# Power.net
KiCad netlist of a schematic drawn in Altium Designer
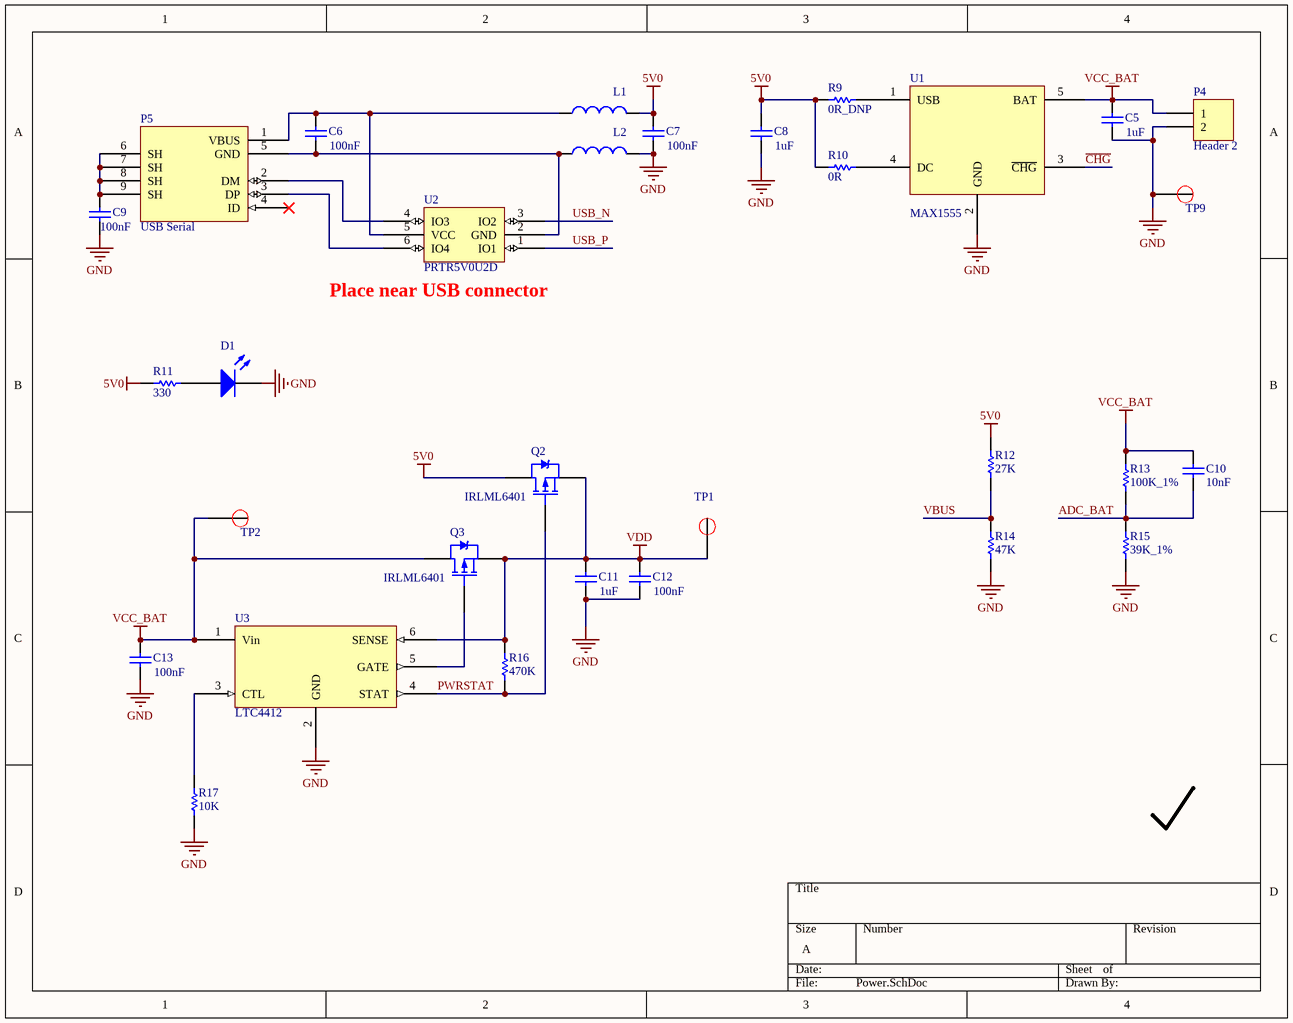
[diagram p0: Power.SchDoc]

(export (version "E")
  (design (tool "Eeschema 10.0.6"))
  (components
    (comp (ref "C5")
      (value "1uF")
      (footprint "0603PKG")
      (description "Capacitor")
      (fields (field (name "Comment") "Cap") (field (name "PUBLISHER") "Altium Limited"))
      (libsource (lib "Miscellaneous Devices") (part "Cap"))
    )
    (comp (ref "C6")
      (value "100nF")
      (footprint "C0805")
      (description "Capacitor")
      (fields (field (name "Comment") "Cap") (field (name "PUBLISHER") "Altium Limited"))
      (libsource (lib "Miscellaneous Devices") (part "Cap"))
    )
    (comp (ref "C7")
      (value "100nF")
      (footprint "C0805")
      (description "Capacitor")
      (fields (field (name "Comment") "Cap") (field (name "PUBLISHER") "Altium Limited"))
      (libsource (lib "Miscellaneous Devices") (part "Cap"))
    )
    (comp (ref "C8")
      (value "1uF")
      (footprint "0603PKG")
      (description "Capacitor")
      (fields (field (name "Comment") "Cap") (field (name "PUBLISHER") "Altium Limited"))
      (libsource (lib "Miscellaneous Devices") (part "Cap"))
    )
    (comp (ref "C9")
      (value "100nF")
      (footprint "C0805")
      (description "Capacitor")
      (fields (field (name "Comment") "Cap") (field (name "PUBLISHER") "Altium Limited"))
      (libsource (lib "Miscellaneous Devices") (part "Cap"))
    )
    (comp (ref "C10")
      (value "10nF")
      (footprint "0603PKG")
      (description "Capacitor (Semiconductor SIM Model)")
      (fields (field (name "Comment") "Cap Semi") (field (name "PUBLISHER") "Altium Limited"))
      (libsource (lib "Miscellaneous Devices") (part "Cap Semi"))
    )
    (comp (ref "C11")
      (value "1uF")
      (footprint "0603PKG")
      (description "Capacitor")
      (fields (field (name "Comment") "Cap") (field (name "PUBLISHER") "Altium Limited"))
      (libsource (lib "Miscellaneous Devices") (part "Cap"))
    )
    (comp (ref "C12")
      (value "100nF")
      (footprint "0603PKG")
      (description "Capacitor")
      (fields (field (name "Comment") "Cap") (field (name "PUBLISHER") "Altium Limited"))
      (libsource (lib "Miscellaneous Devices") (part "Cap"))
    )
    (comp (ref "C13")
      (value "100nF")
      (footprint "0603PKG")
      (description "Capacitor")
      (fields (field (name "Comment") "Cap") (field (name "PUBLISHER") "Altium Limited"))
      (libsource (lib "Miscellaneous Devices") (part "Cap"))
    )
    (comp (ref "D1")
      (value "LED0")
      (footprint "C0805")
      (description "Typical INFRARED GaAs LED")
      (fields (field (name "PUBLISHER") "Altium Limited"))
      (libsource (lib "Miscellaneous Devices") (part "LED0"))
    )
    (comp (ref "L1")
      (value "Ferrite Bead")
      (footprint "C0805")
      (description "Inductor")
      (fields (field (name "PUBLISHER") "Altium Limited"))
      (libsource (lib "Miscellaneous Devices") (part "Inductor"))
    )
    (comp (ref "L2")
      (value "Ferrite Bead")
      (footprint "C0805")
      (description "Inductor")
      (fields (field (name "PUBLISHER") "Altium Limited"))
      (libsource (lib "Miscellaneous Devices") (part "Inductor"))
    )
    (comp (ref "P4")
      (value "Header 2")
      (footprint "XH_2Pin_RA")
      (description "Header, 2-Pin")
      (fields (field (name "PUBLISHER") "Altium Limited"))
      (libsource (lib "Miscellaneous Connectors") (part "Header 2"))
    )
    (comp (ref "P5")
      (value "USB Serial")
      (footprint "Mini USB")
      (libsource (lib "Connector_IntLib") (part "Mini USB"))
    )
    (comp (ref "Q2")
      (value "IRLML6401")
      (footprint "SOT23")
      (description "P-Channel Power MOSFET")
      (fields (field (name "PUBLISHER") "Altium Limited"))
      (libsource (lib "Miscellaneous Devices") (part "PMOS-2"))
    )
    (comp (ref "Q3")
      (value "IRLML6401")
      (footprint "SOT23")
      (description "P-Channel Power MOSFET")
      (fields (field (name "PUBLISHER") "Altium Limited"))
      (libsource (lib "Miscellaneous Devices") (part "PMOS-2"))
    )
    (comp (ref "R9")
      (value "0R_DNP")
      (footprint "0603PKG")
      (description "Semiconductor Resistor")
      (fields (field (name "Comment") "Res Semi") (field (name "PUBLISHER") "Altium Limited"))
      (libsource (lib "Miscellaneous Devices") (part "Res Semi"))
    )
    (comp (ref "R10")
      (value "0R")
      (footprint "0603PKG")
      (description "Semiconductor Resistor")
      (fields (field (name "Comment") "Res Semi") (field (name "PUBLISHER") "Altium Limited"))
      (libsource (lib "Miscellaneous Devices") (part "Res Semi"))
    )
    (comp (ref "R11")
      (value "330")
      (footprint "0603PKG")
      (description "Semiconductor Resistor")
      (fields (field (name "Comment") "Res Semi") (field (name "PUBLISHER") "Altium Limited"))
      (libsource (lib "Miscellaneous Devices") (part "Res Semi"))
    )
    (comp (ref "R12")
      (value "27K")
      (footprint "0603PKG")
      (description "Semiconductor Resistor")
      (fields (field (name "Comment") "Res Semi") (field (name "PUBLISHER") "Altium Limited"))
      (libsource (lib "Miscellaneous Devices") (part "Res Semi"))
    )
    (comp (ref "R13")
      (value "100K_1%")
      (footprint "0603PKG")
      (description "Semiconductor Resistor")
      (fields (field (name "Comment") "Res Semi") (field (name "PUBLISHER") "Altium Limited"))
      (libsource (lib "Miscellaneous Devices") (part "Res Semi"))
    )
    (comp (ref "R14")
      (value "47K")
      (footprint "0603PKG")
      (description "Semiconductor Resistor")
      (fields (field (name "Comment") "Res Semi") (field (name "PUBLISHER") "Altium Limited"))
      (libsource (lib "Miscellaneous Devices") (part "Res Semi"))
    )
    (comp (ref "R15")
      (value "39K_1%")
      (footprint "0603PKG")
      (description "Semiconductor Resistor")
      (fields (field (name "Comment") "Res Semi") (field (name "PUBLISHER") "Altium Limited"))
      (libsource (lib "Miscellaneous Devices") (part "Res Semi"))
    )
    (comp (ref "R16")
      (value "470K")
      (footprint "0603PKG")
      (description "Semiconductor Resistor")
      (fields (field (name "Comment") "Res Semi") (field (name "PUBLISHER") "Altium Limited"))
      (libsource (lib "Miscellaneous Devices") (part "Res Semi"))
    )
    (comp (ref "R17")
      (value "10K")
      (footprint "0603PKG")
      (description "Semiconductor Resistor")
      (fields (field (name "Comment") "Res Semi") (field (name "PUBLISHER") "Altium Limited"))
      (libsource (lib "Miscellaneous Devices") (part "Res Semi"))
    )
    (comp (ref "TP1")
      (value "TP")
      (footprint "TP_15")
      (libsource (lib "Connector_IntLib") (part "Test Point"))
    )
    (comp (ref "TP2")
      (value "TP")
      (footprint "TP_15")
      (libsource (lib "Connector_IntLib") (part "Test Point"))
    )
    (comp (ref "TP9")
      (value "TP")
      (footprint "TP_15")
      (libsource (lib "Connector_IntLib") (part "Test Point"))
    )
    (comp (ref "U1")
      (value "MAX1555")
      (footprint "SOT23-5")
      (description "1-Cell Li+  Battery Chargers")
      (libsource (lib "Connector_IntLib") (part "MAX1555"))
    )
    (comp (ref "U2")
      (value "PRTR5V0U2D")
      (footprint "SOT457")
      (description "TVS Zener")
      (libsource (lib "Connector_IntLib") (part "PRTR5V0U2D"))
    )
    (comp (ref "U3")
      (value "LTC4412")
      (footprint "SOT23-6")
      (description "Low Loss PowerPath™  Controller in ThinSOT")
      (libsource (lib "Connector_IntLib") (part "LTC4412"))
    )
  )
  (nets
    (net (code "1") (name "/ADC_BAT") (class "Default")
      (node (ref "C10") (pin "2") (pinfunction "2_2") (pintype "passive"))
      (node (ref "R13") (pin "1") (pinfunction "1_1") (pintype "passive"))
      (node (ref "R15") (pin "2") (pinfunction "2_2") (pintype "passive"))
    )
    (net (code "2") (name "/PWRSTAT") (class "Default")
      (node (ref "Q2") (pin "1") (pinfunction "G_1") (pintype "passive"))
      (node (ref "R16") (pin "1") (pinfunction "1_1") (pintype "passive"))
      (node (ref "U3") (pin "4") (pinfunction "STAT_4") (pintype "output"))
    )
    (net (code "3") (name "/USB_N") (class "Default")
      (node (ref "U2") (pin "3") (pinfunction "IO2_3") (pintype "bidirectional"))
    )
    (net (code "4") (name "/USB_P") (class "Default")
      (node (ref "U2") (pin "1") (pinfunction "IO1_1") (pintype "bidirectional"))
    )
    (net (code "5") (name "/VBUS") (class "Default")
      (node (ref "R12") (pin "1") (pinfunction "1_1") (pintype "passive"))
      (node (ref "R14") (pin "2") (pinfunction "2_2") (pintype "passive"))
    )
    (net (code "6") (name "/~{CHG}") (class "Default")
      (node (ref "U1") (pin "3") (pinfunction "~{CHG}_3") (pintype "open_collector"))
    )
    (net (code "7") (name "5V0") (class "Default")
      (node (ref "C7") (pin "2") (pinfunction "2_2") (pintype "passive"))
      (node (ref "C8") (pin "2") (pinfunction "2_2") (pintype "passive"))
      (node (ref "L1") (pin "2") (pinfunction "2_2") (pintype "passive"))
      (node (ref "Q2") (pin "3") (pinfunction "D_3") (pintype "passive"))
      (node (ref "R10") (pin "1") (pinfunction "1_1") (pintype "passive"))
      (node (ref "R11") (pin "2") (pinfunction "2_2") (pintype "passive"))
      (node (ref "R12") (pin "2") (pinfunction "2_2") (pintype "passive"))
      (node (ref "R9") (pin "1") (pinfunction "1_1") (pintype "passive"))
    )
    (net (code "8") (name "GND") (class "Default")
      (node (ref "C11") (pin "1") (pinfunction "1_1") (pintype "passive"))
      (node (ref "C12") (pin "1") (pinfunction "1_1") (pintype "passive"))
      (node (ref "C13") (pin "1") (pinfunction "1_1") (pintype "passive"))
      (node (ref "C5") (pin "1") (pinfunction "1_1") (pintype "passive"))
      (node (ref "C7") (pin "1") (pinfunction "1_1") (pintype "passive"))
      (node (ref "C8") (pin "1") (pinfunction "1_1") (pintype "passive"))
      (node (ref "C9") (pin "1") (pinfunction "1_1") (pintype "passive"))
      (node (ref "D1") (pin "2") (pinfunction "K_2") (pintype "passive"))
      (node (ref "L2") (pin "2") (pinfunction "2_2") (pintype "passive"))
      (node (ref "P4") (pin "2") (pinfunction "2_2") (pintype "passive"))
      (node (ref "R14") (pin "1") (pinfunction "1_1") (pintype "passive"))
      (node (ref "R15") (pin "1") (pinfunction "1_1") (pintype "passive"))
      (node (ref "R17") (pin "1") (pinfunction "1_1") (pintype "passive"))
      (node (ref "TP9") (pin "1") (pinfunction "1_1") (pintype "passive"))
      (node (ref "U1") (pin "2") (pinfunction "GND_2") (pintype "power_in"))
      (node (ref "U3") (pin "2") (pinfunction "GND_2") (pintype "power_in"))
    )
    (net (code "9") (name "Net-(C9-Pad2)") (class "Default")
      (node (ref "C9") (pin "2") (pinfunction "2_2") (pintype "passive"))
      (node (ref "P5") (pin "6") (pinfunction "SH_6") (pintype "passive"))
      (node (ref "P5") (pin "7") (pinfunction "SH_7") (pintype "passive"))
      (node (ref "P5") (pin "8") (pinfunction "SH_8") (pintype "passive"))
      (node (ref "P5") (pin "9") (pinfunction "SH_9") (pintype "passive"))
    )
    (net (code "10") (name "Net-(D1-A)") (class "Default")
      (node (ref "D1") (pin "1") (pinfunction "A_1") (pintype "passive"))
      (node (ref "R11") (pin "1") (pinfunction "1_1") (pintype "passive"))
    )
    (net (code "11") (name "Net-(P5-DM)") (class "Default")
      (node (ref "P5") (pin "2") (pinfunction "DM_2") (pintype "bidirectional"))
      (node (ref "U2") (pin "4") (pinfunction "IO3_4") (pintype "bidirectional"))
    )
    (net (code "12") (name "Net-(P5-DP)") (class "Default")
      (node (ref "P5") (pin "3") (pinfunction "DP_3") (pintype "bidirectional"))
      (node (ref "U2") (pin "6") (pinfunction "IO4_6") (pintype "bidirectional"))
    )
    (net (code "13") (name "Net-(P5-GND)") (class "Default")
      (node (ref "C6") (pin "1") (pinfunction "1_1") (pintype "passive"))
      (node (ref "L2") (pin "1") (pinfunction "1_1") (pintype "passive"))
      (node (ref "P5") (pin "5") (pinfunction "GND_5") (pintype "power_in"))
      (node (ref "U2") (pin "2") (pinfunction "GND_2") (pintype "power_in"))
    )
    (net (code "14") (name "Net-(P5-VBUS)") (class "Default")
      (node (ref "C6") (pin "2") (pinfunction "2_2") (pintype "passive"))
      (node (ref "L1") (pin "1") (pinfunction "1_1") (pintype "passive"))
      (node (ref "P5") (pin "1") (pinfunction "VBUS_1") (pintype "power_in"))
      (node (ref "U2") (pin "5") (pinfunction "VCC_5") (pintype "power_in"))
    )
    (net (code "15") (name "Net-(Q3-G)") (class "Default")
      (node (ref "Q3") (pin "1") (pinfunction "G_1") (pintype "passive"))
      (node (ref "U3") (pin "5") (pinfunction "GATE_5") (pintype "output"))
    )
    (net (code "16") (name "Net-(U1-DC)") (class "Default")
      (node (ref "R10") (pin "2") (pinfunction "2_2") (pintype "passive"))
      (node (ref "U1") (pin "4") (pinfunction "DC_4") (pintype "power_in"))
    )
    (net (code "17") (name "Net-(U1-USB)") (class "Default")
      (node (ref "R9") (pin "2") (pinfunction "2_2") (pintype "passive"))
      (node (ref "U1") (pin "1") (pinfunction "USB_1") (pintype "power_in"))
    )
    (net (code "18") (name "Net-(U3-CTL)") (class "Default")
      (node (ref "R17") (pin "2") (pinfunction "2_2") (pintype "passive"))
      (node (ref "U3") (pin "3") (pinfunction "CTL_3") (pintype "input"))
    )
    (net (code "19") (name "VCC_BAT") (class "Default")
      (node (ref "C10") (pin "1") (pinfunction "1_1") (pintype "passive"))
      (node (ref "C13") (pin "2") (pinfunction "2_2") (pintype "passive"))
      (node (ref "C5") (pin "2") (pinfunction "2_2") (pintype "passive"))
      (node (ref "P4") (pin "1") (pinfunction "1_1") (pintype "passive"))
      (node (ref "Q3") (pin "3") (pinfunction "D_3") (pintype "passive"))
      (node (ref "R13") (pin "2") (pinfunction "2_2") (pintype "passive"))
      (node (ref "TP2") (pin "1") (pinfunction "1_1") (pintype "passive"))
      (node (ref "U1") (pin "5") (pinfunction "BAT_5") (pintype "power_in"))
      (node (ref "U3") (pin "1") (pinfunction "Vin_1") (pintype "power_in"))
    )
    (net (code "20") (name "VDD") (class "Default")
      (node (ref "C11") (pin "2") (pinfunction "2_2") (pintype "passive"))
      (node (ref "C12") (pin "2") (pinfunction "2_2") (pintype "passive"))
      (node (ref "Q2") (pin "2") (pinfunction "S_2") (pintype "passive"))
      (node (ref "Q3") (pin "2") (pinfunction "S_2") (pintype "passive"))
      (node (ref "R16") (pin "2") (pinfunction "2_2") (pintype "passive"))
      (node (ref "TP1") (pin "1") (pinfunction "1_1") (pintype "passive"))
      (node (ref "U3") (pin "6") (pinfunction "SENSE_6") (pintype "input"))
    )
    (net (code "21") (name "unconnected-(P5-ID-Pad4)") (class "Default")
      (node (ref "P5") (pin "4") (pinfunction "ID_4") (pintype "input+no_connect"))
    )
  )
)
